# sensorboard_lightning_rev0.net
KiCad netlist of a schematic drawn in EAGLE
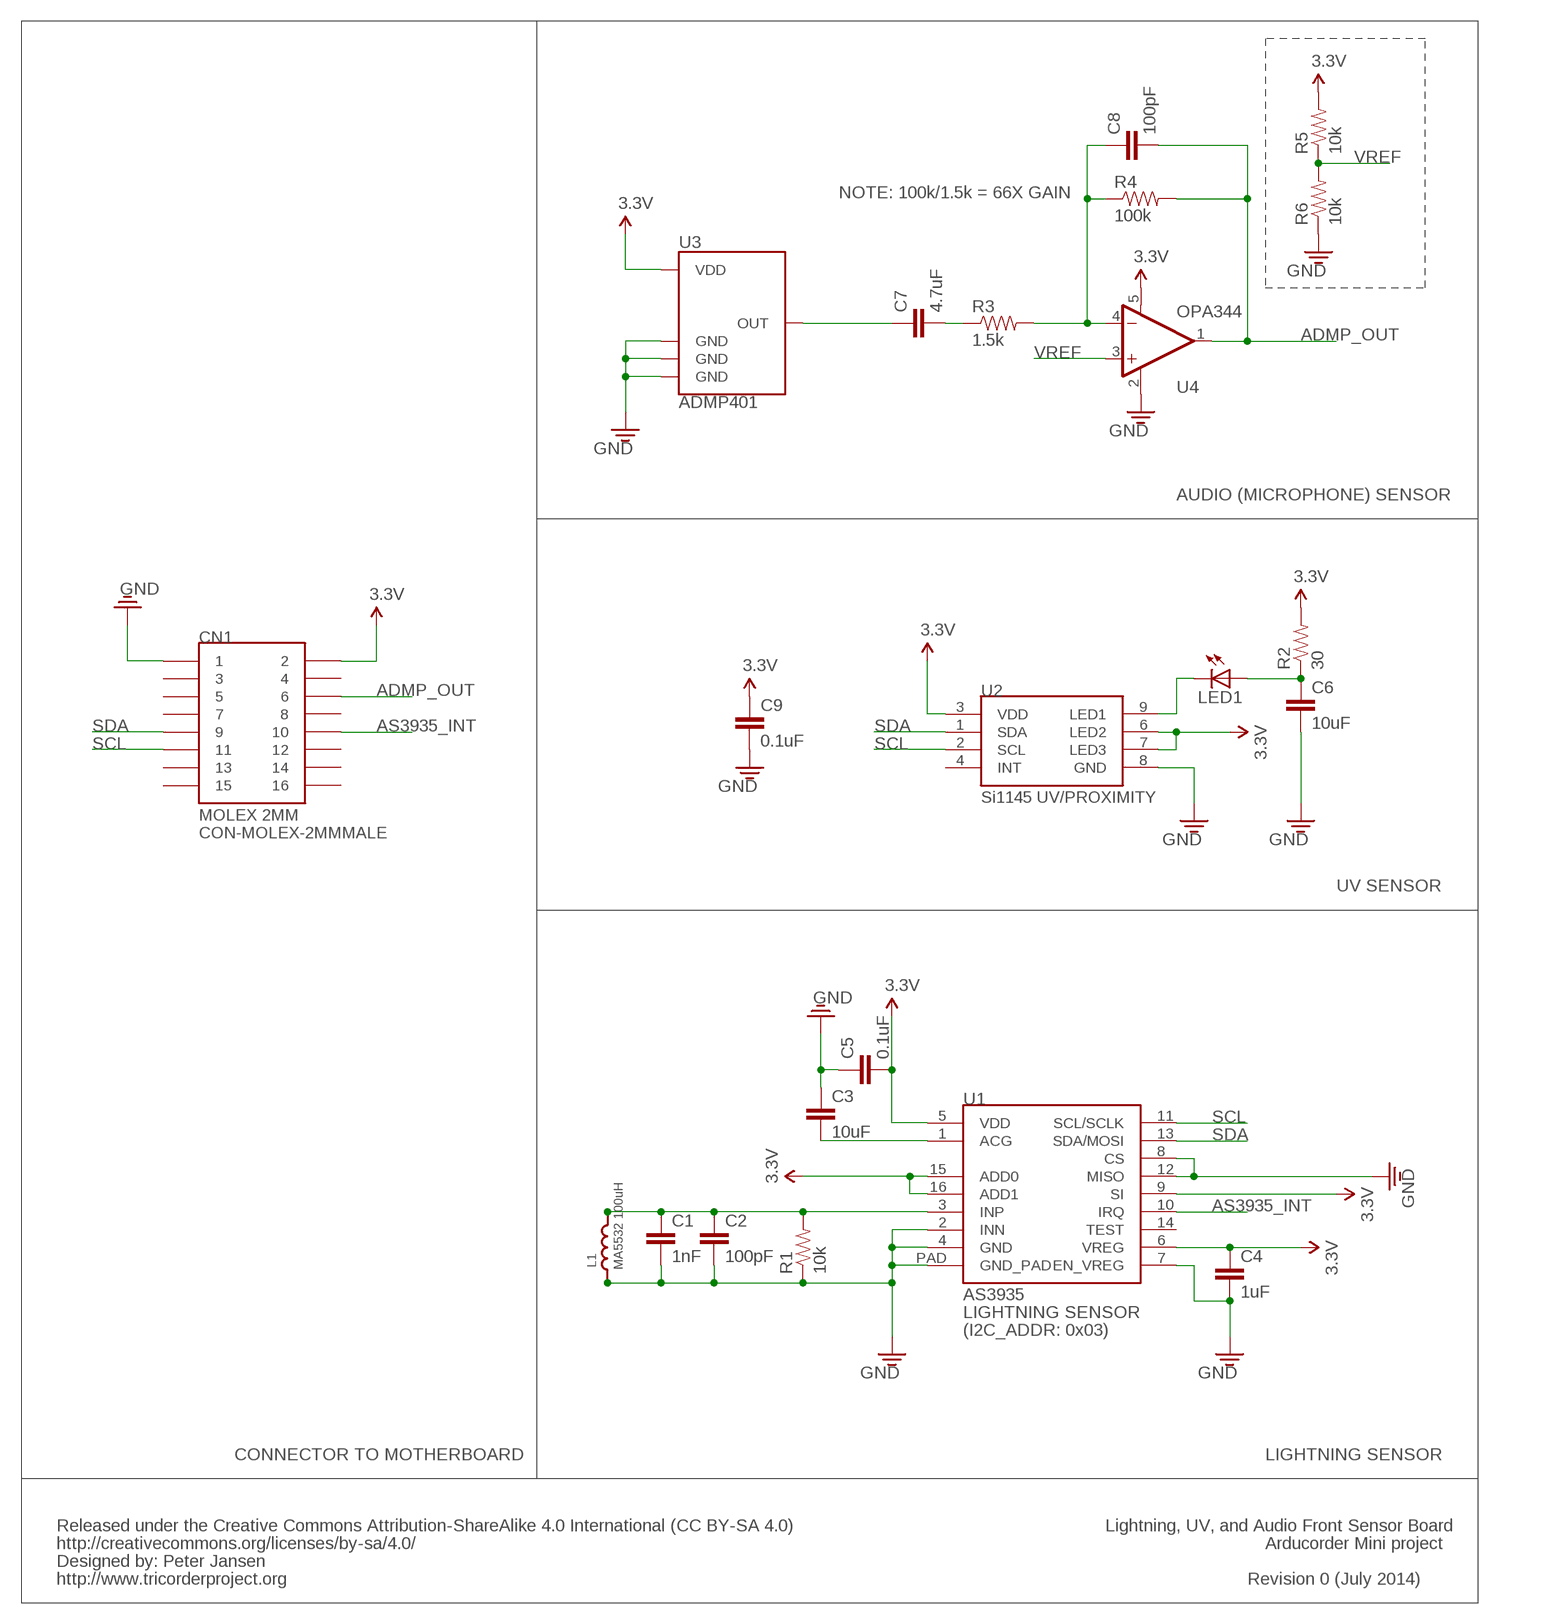
[diagram p0: schematic, sheet 1]

(export (version "E")
  (design (tool "Eeschema 10.0.6"))
  (components
    (comp (ref "C1")
      (value "1nF")
      (footprint "eagle-import:0603")
      (libsource (lib "eagle-import") (part "CAP0603"))
    )
    (comp (ref "C2")
      (value "100pF")
      (footprint "eagle-import:0603")
      (libsource (lib "eagle-import") (part "CAP0603"))
    )
    (comp (ref "C3")
      (value "10uF")
      (footprint "eagle-import:0603")
      (libsource (lib "eagle-import") (part "CAP0603"))
    )
    (comp (ref "C4")
      (value "1uF")
      (footprint "eagle-import:0603")
      (libsource (lib "eagle-import") (part "CAP0603"))
    )
    (comp (ref "C5")
      (value "0.1uF")
      (footprint "eagle-import:0603")
      (libsource (lib "eagle-import") (part "CAP0603"))
    )
    (comp (ref "C6")
      (value "10uF")
      (footprint "eagle-import:0603")
      (libsource (lib "eagle-import") (part "CAP0603"))
    )
    (comp (ref "C7")
      (value "4.7uF")
      (footprint "eagle-import:0603")
      (libsource (lib "eagle-import") (part "notes_mark5a_CAP0603"))
    )
    (comp (ref "C8")
      (value "100pF")
      (footprint "eagle-import:0603")
      (libsource (lib "eagle-import") (part "notes_mark5a_CAP0603"))
    )
    (comp (ref "C9")
      (value "0.1uF")
      (footprint "eagle-import:0603")
      (libsource (lib "eagle-import") (part "CAP0603"))
    )
    (comp (ref "CN1")
      (value "CON-MOLEX-2MMMALE")
      (footprint "eagle-import:MOLEX-0877591650")
      (libsource (lib "eagle-import") (part "CON-MOLEX-2MMMALE"))
    )
    (comp (ref "L1")
      (value "MA5532 100uH")
      (footprint "eagle-import:MA5532-AE")
      (libsource (lib "eagle-import") (part "INDUCTOR"))
    )
    (comp (ref "LED1")
      (value "LED1206")
      (footprint "eagle-import:LED-1206")
      (libsource (lib "eagle-import") (part "LED1206"))
    )
    (comp (ref "R1")
      (value "10k")
      (footprint "eagle-import:0603")
      (libsource (lib "eagle-import") (part "RESISTOR0603"))
    )
    (comp (ref "R2")
      (value "30")
      (footprint "eagle-import:0603")
      (libsource (lib "eagle-import") (part "RESISTOR0603"))
    )
    (comp (ref "R3")
      (value "1.5k")
      (footprint "eagle-import:0603")
      (libsource (lib "eagle-import") (part "notes_mark5a_RESISTOR0603"))
    )
    (comp (ref "R4")
      (value "100k")
      (footprint "eagle-import:0603")
      (libsource (lib "eagle-import") (part "notes_mark5a_RESISTOR0603"))
    )
    (comp (ref "R5")
      (value "10k")
      (footprint "eagle-import:0603")
      (libsource (lib "eagle-import") (part "notes_mark5a_RESISTOR0603"))
    )
    (comp (ref "R6")
      (value "10k")
      (footprint "eagle-import:0603")
      (libsource (lib "eagle-import") (part "notes_mark5a_RESISTOR0603"))
    )
    (comp (ref "U1")
      (value "AS3935")
      (footprint "eagle-import:16LD_MLPQ-(4X4MM)")
      (libsource (lib "eagle-import") (part "AS3935"))
    )
    (comp (ref "U2")
      (value "SI1145")
      (footprint "eagle-import:SI1145")
      (libsource (lib "eagle-import") (part "SI1145"))
    )
    (comp (ref "U3")
      (value "ADMP401")
      (footprint "eagle-import:ADMP401")
      (libsource (lib "eagle-import") (part "ADMP401"))
    )
    (comp (ref "U4")
      (value "OPA344")
      (footprint "eagle-import:SOT23-5")
      (libsource (lib "eagle-import") (part "OPA344"))
    )
  )
  (nets
    (net (code "1") (name "/ADMP_OUT") (class "Default")
      (node (ref "C8") (pin "2") (pinfunction "2_2") (pintype "passive"))
      (node (ref "CN1") (pin "6") (pinfunction "6_6") (pintype "bidirectional"))
      (node (ref "R4") (pin "2") (pinfunction "2_2") (pintype "passive"))
      (node (ref "U4") (pin "1") (pinfunction "OUT_1") (pintype "output"))
    )
    (net (code "2") (name "/AS3935_INT") (class "Default")
      (node (ref "CN1") (pin "10") (pinfunction "10_10") (pintype "bidirectional"))
      (node (ref "U1") (pin "10") (pinfunction "IRQ_10") (pintype "bidirectional"))
    )
    (net (code "3") (name "/SCL") (class "Default")
      (node (ref "CN1") (pin "11") (pinfunction "11_11") (pintype "bidirectional"))
      (node (ref "U1") (pin "11") (pinfunction "SCL/SCLK_11") (pintype "bidirectional"))
      (node (ref "U2") (pin "2") (pinfunction "SCL_2") (pintype "bidirectional"))
    )
    (net (code "4") (name "/SDA") (class "Default")
      (node (ref "CN1") (pin "9") (pinfunction "9_9") (pintype "bidirectional"))
      (node (ref "U1") (pin "13") (pinfunction "SDA/MOSI_13") (pintype "bidirectional"))
      (node (ref "U2") (pin "1") (pinfunction "SDA_1") (pintype "bidirectional"))
    )
    (net (code "5") (name "/VREF") (class "Default")
      (node (ref "R5") (pin "1") (pinfunction "1_1") (pintype "passive"))
      (node (ref "R6") (pin "2") (pinfunction "2_2") (pintype "passive"))
      (node (ref "U4") (pin "3") (pinfunction "+IN_3") (pintype "input"))
    )
    (net (code "6") (name "3.3V") (class "Default")
      (node (ref "C4") (pin "1") (pinfunction "1_1") (pintype "passive"))
      (node (ref "C5") (pin "2") (pinfunction "2_2") (pintype "passive"))
      (node (ref "C9") (pin "1") (pinfunction "1_1") (pintype "passive"))
      (node (ref "CN1") (pin "2") (pinfunction "2_2") (pintype "bidirectional"))
      (node (ref "R2") (pin "2") (pinfunction "2_2") (pintype "passive"))
      (node (ref "R5") (pin "2") (pinfunction "2_2") (pintype "passive"))
      (node (ref "U1") (pin "15") (pinfunction "ADD0_15") (pintype "bidirectional"))
      (node (ref "U1") (pin "16") (pinfunction "ADD1_16") (pintype "bidirectional"))
      (node (ref "U1") (pin "5") (pinfunction "VDD_5") (pintype "bidirectional"))
      (node (ref "U1") (pin "6") (pinfunction "VREG_6") (pintype "bidirectional"))
      (node (ref "U1") (pin "9") (pinfunction "SI_9") (pintype "bidirectional"))
      (node (ref "U2") (pin "3") (pinfunction "VDD_3") (pintype "bidirectional"))
      (node (ref "U2") (pin "6") (pinfunction "LED2_6") (pintype "bidirectional"))
      (node (ref "U2") (pin "7") (pinfunction "LED3_7") (pintype "bidirectional"))
      (node (ref "U3") (pin "5") (pinfunction "VDD_5") (pintype "bidirectional"))
      (node (ref "U4") (pin "5") (pinfunction "V+_5") (pintype "power_in"))
    )
    (net (code "7") (name "GND") (class "Default")
      (node (ref "C1") (pin "2") (pinfunction "2_2") (pintype "passive"))
      (node (ref "C2") (pin "2") (pinfunction "2_2") (pintype "passive"))
      (node (ref "C3") (pin "1") (pinfunction "1_1") (pintype "passive"))
      (node (ref "C4") (pin "2") (pinfunction "2_2") (pintype "passive"))
      (node (ref "C5") (pin "1") (pinfunction "1_1") (pintype "passive"))
      (node (ref "C6") (pin "2") (pinfunction "2_2") (pintype "passive"))
      (node (ref "C9") (pin "2") (pinfunction "2_2") (pintype "passive"))
      (node (ref "CN1") (pin "1") (pinfunction "1_1") (pintype "bidirectional"))
      (node (ref "L1") (pin "2") (pinfunction "2_2") (pintype "bidirectional"))
      (node (ref "R1") (pin "1") (pinfunction "1_1") (pintype "passive"))
      (node (ref "R6") (pin "1") (pinfunction "1_1") (pintype "passive"))
      (node (ref "U1") (pin "12") (pinfunction "MISO_12") (pintype "bidirectional"))
      (node (ref "U1") (pin "2") (pinfunction "INN_2") (pintype "bidirectional"))
      (node (ref "U1") (pin "4") (pinfunction "GND_4") (pintype "bidirectional"))
      (node (ref "U1") (pin "7") (pinfunction "EN_VREG_7") (pintype "bidirectional"))
      (node (ref "U1") (pin "8") (pinfunction "CS_8") (pintype "bidirectional"))
      (node (ref "U1") (pin "PAD") (pinfunction "GND_PAD_PAD") (pintype "bidirectional"))
      (node (ref "U2") (pin "8") (pinfunction "GND_8") (pintype "bidirectional"))
      (node (ref "U3") (pin "2") (pinfunction "GND_2") (pintype "bidirectional"))
      (node (ref "U3") (pin "4") (pinfunction "GND_4") (pintype "bidirectional"))
      (node (ref "U3") (pin "6") (pinfunction "GND_6") (pintype "bidirectional"))
      (node (ref "U4") (pin "2") (pinfunction "V-_2") (pintype "power_in"))
    )
    (net (code "8") (name "Net-(C6-Pad1)") (class "Default")
      (node (ref "C6") (pin "1") (pinfunction "1_1") (pintype "passive"))
      (node (ref "LED1") (pin "A") (pinfunction "A_A") (pintype "passive"))
      (node (ref "R2") (pin "1") (pinfunction "1_1") (pintype "passive"))
    )
    (net (code "9") (name "Net-(C7-Pad2)") (class "Default")
      (node (ref "C7") (pin "2") (pinfunction "2_2") (pintype "passive"))
      (node (ref "R3") (pin "1") (pinfunction "1_1") (pintype "passive"))
    )
    (net (code "10") (name "Net-(U1-ACG)") (class "Default")
      (node (ref "C3") (pin "2") (pinfunction "2_2") (pintype "passive"))
      (node (ref "U1") (pin "1") (pinfunction "ACG_1") (pintype "bidirectional"))
    )
    (net (code "11") (name "Net-(U1-INP)") (class "Default")
      (node (ref "C1") (pin "1") (pinfunction "1_1") (pintype "passive"))
      (node (ref "C2") (pin "1") (pinfunction "1_1") (pintype "passive"))
      (node (ref "L1") (pin "1") (pinfunction "1_1") (pintype "bidirectional"))
      (node (ref "R1") (pin "2") (pinfunction "2_2") (pintype "passive"))
      (node (ref "U1") (pin "3") (pinfunction "INP_3") (pintype "bidirectional"))
    )
    (net (code "12") (name "Net-(U2-LED1)") (class "Default")
      (node (ref "LED1") (pin "C") (pinfunction "C_C") (pintype "passive"))
      (node (ref "U2") (pin "9") (pinfunction "LED1_9") (pintype "bidirectional"))
    )
    (net (code "13") (name "Net-(U3-OUT)") (class "Default")
      (node (ref "C7") (pin "1") (pinfunction "1_1") (pintype "passive"))
      (node (ref "U3") (pin "1") (pinfunction "OUT_1") (pintype "bidirectional"))
    )
    (net (code "14") (name "Net-(U4--IN)") (class "Default")
      (node (ref "C8") (pin "1") (pinfunction "1_1") (pintype "passive"))
      (node (ref "R3") (pin "2") (pinfunction "2_2") (pintype "passive"))
      (node (ref "R4") (pin "1") (pinfunction "1_1") (pintype "passive"))
      (node (ref "U4") (pin "4") (pinfunction "-IN_4") (pintype "input"))
    )
    (net (code "15") (name "unconnected-(CN1-Pad3)") (class "Default")
      (node (ref "CN1") (pin "3") (pinfunction "3_3") (pintype "bidirectional"))
    )
    (net (code "16") (name "unconnected-(CN1-Pad4)") (class "Default")
      (node (ref "CN1") (pin "4") (pinfunction "4_4") (pintype "bidirectional"))
    )
    (net (code "17") (name "unconnected-(CN1-Pad5)") (class "Default")
      (node (ref "CN1") (pin "5") (pinfunction "5_5") (pintype "bidirectional"))
    )
    (net (code "18") (name "unconnected-(CN1-Pad7)") (class "Default")
      (node (ref "CN1") (pin "7") (pinfunction "7_7") (pintype "bidirectional"))
    )
    (net (code "19") (name "unconnected-(CN1-Pad8)") (class "Default")
      (node (ref "CN1") (pin "8") (pinfunction "8_8") (pintype "bidirectional"))
    )
    (net (code "20") (name "unconnected-(CN1-Pad12)") (class "Default")
      (node (ref "CN1") (pin "12") (pinfunction "12_12") (pintype "bidirectional"))
    )
    (net (code "21") (name "unconnected-(CN1-Pad13)") (class "Default")
      (node (ref "CN1") (pin "13") (pinfunction "13_13") (pintype "bidirectional"))
    )
    (net (code "22") (name "unconnected-(CN1-Pad14)") (class "Default")
      (node (ref "CN1") (pin "14") (pinfunction "14_14") (pintype "bidirectional"))
    )
    (net (code "23") (name "unconnected-(CN1-Pad15)") (class "Default")
      (node (ref "CN1") (pin "15") (pinfunction "15_15") (pintype "bidirectional"))
    )
    (net (code "24") (name "unconnected-(CN1-Pad16)") (class "Default")
      (node (ref "CN1") (pin "16") (pinfunction "16_16") (pintype "bidirectional"))
    )
    (net (code "25") (name "unconnected-(U1-TEST-Pad14)") (class "Default")
      (node (ref "U1") (pin "14") (pinfunction "TEST_14") (pintype "bidirectional"))
    )
    (net (code "26") (name "unconnected-(U2-INT-Pad4)") (class "Default")
      (node (ref "U2") (pin "4") (pinfunction "INT_4") (pintype "bidirectional"))
    )
  )
)
